# Decimal_Display_Electronic_Scheme_2021-1.net
KiCad netlist of a schematic drawn in Altium Designer
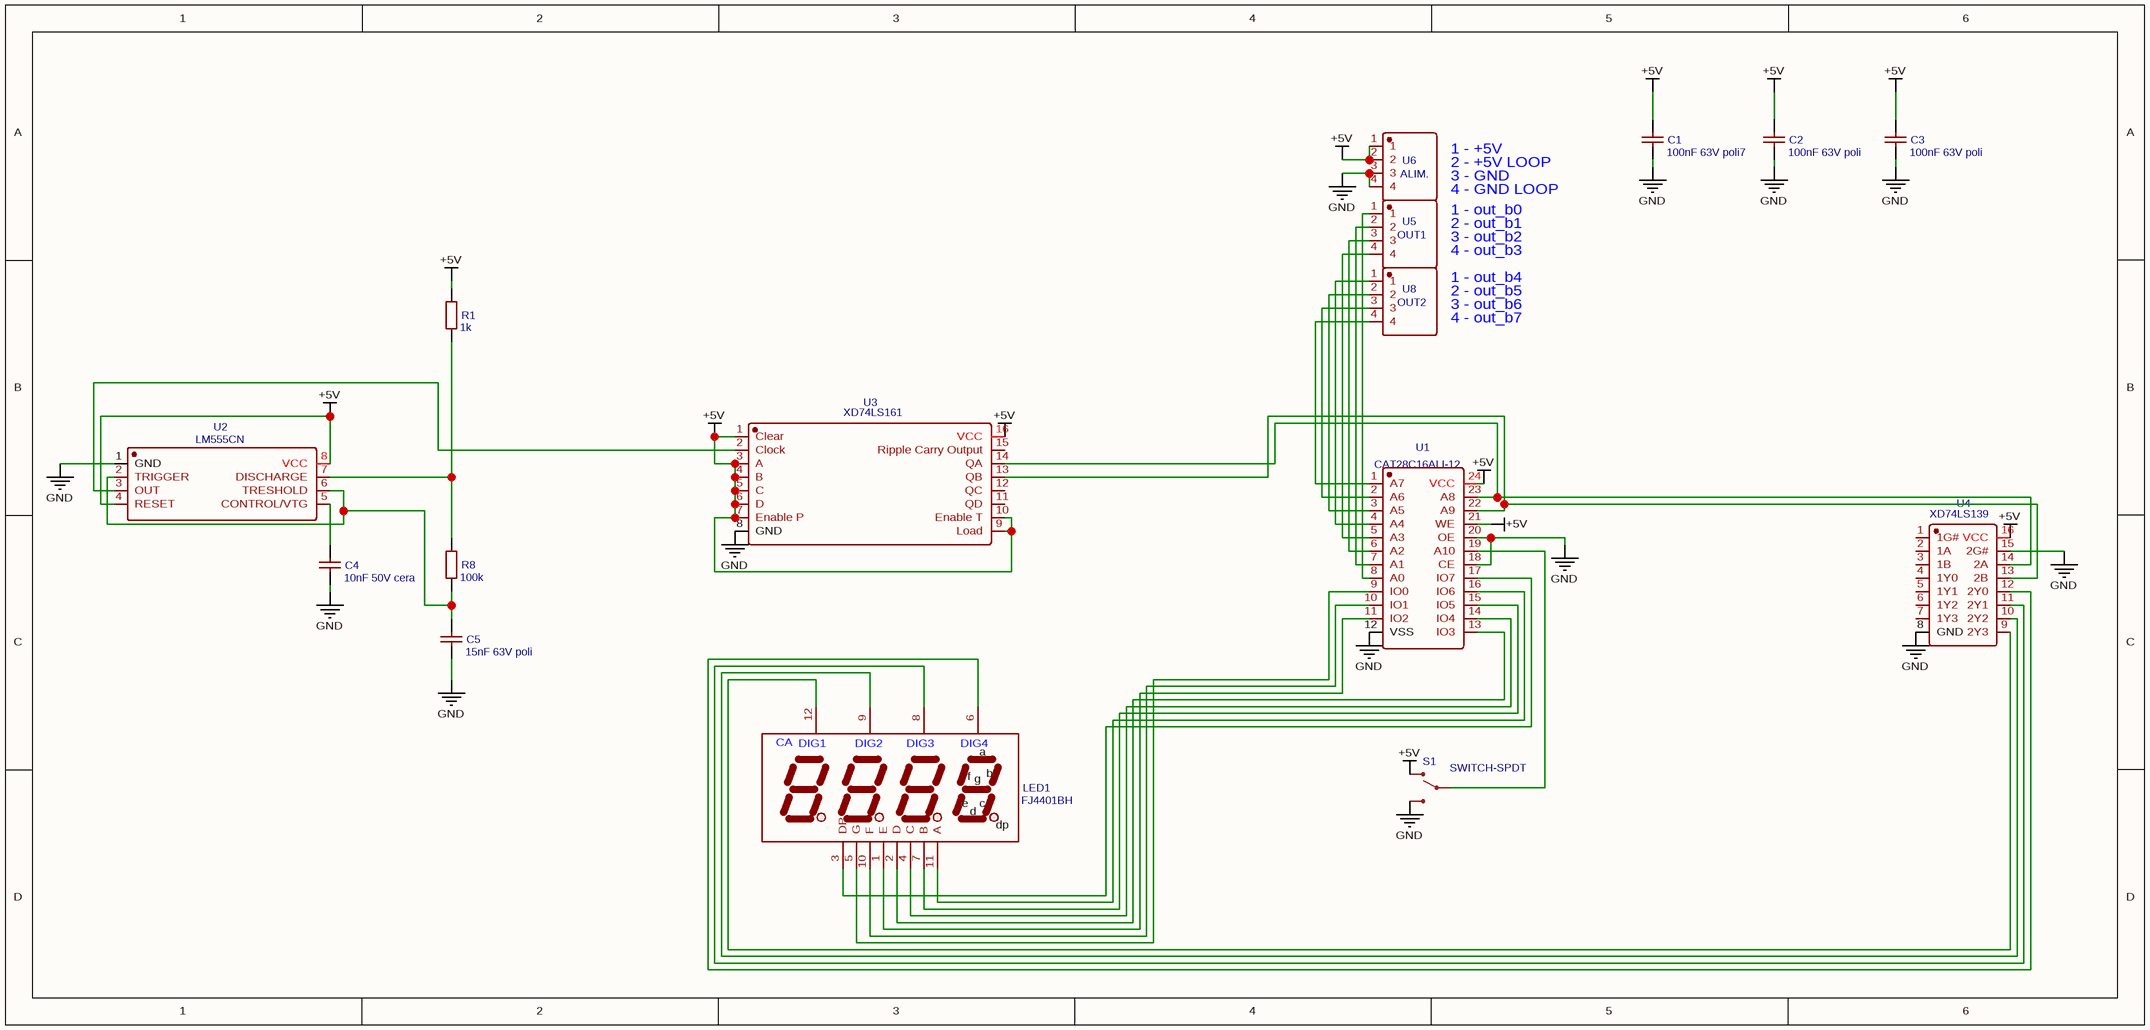
[diagram p0: Decimal Display Electronic Scheme_2021-10-08.schdoc]

(export (version "E")
  (design (tool "Eeschema 10.0.6"))
  (components
    (comp (ref "C1")
      (value "100nF 63V poli7")
      (fields
        (field (name "BOM_SUPPLIER PART") "C444741")
        (field (name "BOM_MANUFACTURER PART") "SR305C105KAR")
        (field (name "CONTRIBUTOR") "LCSC")
      )
      (libsource (lib "altium-import") (part "root_3_100nF 63V poli7_"))
    )
    (comp (ref "C2")
      (value "100nF 63V poli")
      (fields
        (field (name "BOM_SUPPLIER PART") "C444741")
        (field (name "BOM_MANUFACTURER PART") "SR305C105KAR")
        (field (name "CONTRIBUTOR") "LCSC")
      )
      (libsource (lib "altium-import") (part "root_3_100nF 63V poli_"))
    )
    (comp (ref "C3")
      (value "100nF 63V poli")
      (fields
        (field (name "BOM_SUPPLIER PART") "C444741")
        (field (name "BOM_MANUFACTURER PART") "SR305C105KAR")
        (field (name "CONTRIBUTOR") "LCSC")
      )
      (libsource (lib "altium-import") (part "root_3_100nF 63V poli_"))
    )
    (comp (ref "C4")
      (value "10nF 50V cera")
      (fields
        (field (name "BOM_SUPPLIER PART") "C444741")
        (field (name "BOM_MANUFACTURER PART") "SR305C105KAR")
        (field (name "CONTRIBUTOR") "LCSC")
      )
      (libsource (lib "altium-import") (part "root_3_10nF 50V cera_"))
    )
    (comp (ref "C5")
      (value "15nF 63V poli")
      (fields
        (field (name "BOM_SUPPLIER PART") "C444741")
        (field (name "BOM_MANUFACTURER PART") "SR305C105KAR")
        (field (name "CONTRIBUTOR") "LCSC")
      )
      (libsource (lib "altium-import") (part "root_3_15nF 63V poli_"))
    )
    (comp (ref "LED1")
      (value "FJ4401BH")
      (fields (field (name "BOM_SUPPLIER PART") "C10712"))
      (libsource (lib "altium-import") (part "root_0_FJ4401BH_"))
    )
    (comp (ref "R1")
      (value "1k")
      (fields
        (field (name "BOM_MANUFACTURER PART") "CFR02SJ0823A10")
        (field (name "BOM_SUPPLIER PART") "C69876")
      )
      (libsource (lib "altium-import") (part "root_3_1k_"))
    )
    (comp (ref "R8")
      (value "100k")
      (fields
        (field (name "BOM_MANUFACTURER PART") "CFR02SJ0823A10")
        (field (name "BOM_SUPPLIER PART") "C69876")
      )
      (libsource (lib "altium-import") (part "root_3_100k_"))
    )
    (comp (ref "S1")
      (value "SWITCH-SPDT")
      (fields (field (name "CONTRIBUTOR") "SparkFun"))
      (libsource (lib "altium-import") (part "root_0_SWITCH-SPDT_"))
    )
    (comp (ref "U1")
      (value "CAT28C16ALI-12")
      (libsource (lib "altium-import") (part "root_0_CAT28C16ALI-12_"))
    )
    (comp (ref "U2")
      (value "LM555CN")
      (fields (field (name "BOM_SUPPLIER PART") "C110322"))
      (libsource (lib "altium-import") (part "root_0_LM555CN_"))
    )
    (comp (ref "U3")
      (value "XD74LS161")
      (fields (field (name "BOM_SUPPLIER PART") "C609766") (field (name "CONTRIBUTOR") "LCSC"))
      (libsource (lib "altium-import") (part "root_0_XD74LS161_"))
    )
    (comp (ref "U4")
      (value "XD74LS139")
      (fields (field (name "BOM_SUPPLIER PART") "C521175") (field (name "CONTRIBUTOR") "LCSC"))
      (libsource (lib "altium-import") (part "root_0_XD74LS139_"))
    )
    (comp (ref "U5")
      (value "OUT1")
      (fields
        (field (name "BOM_SUPPLIER PART") "C210162")
        (field (name "BOM_MANUFACTURER PART") "171825-4")
        (field (name "CONTRIBUTOR") "LCSC")
      )
      (libsource (lib "altium-import") (part "root_0_OUT1_"))
    )
    (comp (ref "U6")
      (value "ALIM.")
      (fields
        (field (name "BOM_SUPPLIER PART") "C210162")
        (field (name "BOM_MANUFACTURER PART") "171825-4")
        (field (name "CONTRIBUTOR") "LCSC")
      )
      (libsource (lib "altium-import") (part "root_0_ALIM._"))
    )
    (comp (ref "U8")
      (value "OUT2")
      (fields
        (field (name "BOM_SUPPLIER PART") "C210162")
        (field (name "BOM_MANUFACTURER PART") "171825-4")
        (field (name "CONTRIBUTOR") "LCSC")
      )
      (libsource (lib "altium-import") (part "root_0_OUT2_"))
    )
  )
  (nets
    (net (code "1") (name "+5V") (class "Default")
      (node (ref "C1") (pin "1") (pinfunction "1_1") (pintype "passive"))
      (node (ref "C2") (pin "1") (pinfunction "1_1") (pintype "passive"))
      (node (ref "C3") (pin "1") (pinfunction "1_1") (pintype "passive"))
      (node (ref "R1") (pin "1") (pinfunction "1_1") (pintype "passive"))
      (node (ref "S1") (pin "1") (pinfunction "O_1") (pintype "passive"))
      (node (ref "U1") (pin "21") (pinfunction "WE_21") (pintype "passive"))
      (node (ref "U1") (pin "24") (pinfunction "VCC_24") (pintype "passive"))
      (node (ref "U2") (pin "4") (pinfunction "RESET_4") (pintype "passive"))
      (node (ref "U2") (pin "8") (pinfunction "VCC_8") (pintype "passive"))
      (node (ref "U3") (pin "1") (pinfunction "Clear_1") (pintype "passive"))
      (node (ref "U3") (pin "10") (pinfunction "Enable_T_10") (pintype "passive"))
      (node (ref "U3") (pin "16") (pinfunction "VCC_16") (pintype "passive"))
      (node (ref "U3") (pin "3") (pinfunction "A_3") (pintype "passive"))
      (node (ref "U3") (pin "4") (pinfunction "B_4") (pintype "passive"))
      (node (ref "U3") (pin "5") (pinfunction "C_5") (pintype "passive"))
      (node (ref "U3") (pin "6") (pinfunction "D_6") (pintype "passive"))
      (node (ref "U3") (pin "7") (pinfunction "Enable_P_7") (pintype "passive"))
      (node (ref "U3") (pin "9") (pinfunction "Load_9") (pintype "passive"))
      (node (ref "U4") (pin "16") (pinfunction "VCC_16") (pintype "passive"))
      (node (ref "U6") (pin "1") (pinfunction "1_1") (pintype "passive"))
      (node (ref "U6") (pin "2") (pinfunction "2_2") (pintype "passive"))
    )
    (net (code "2") (name "GND") (class "Default")
      (node (ref "C1") (pin "2") (pinfunction "2_2") (pintype "passive"))
      (node (ref "C2") (pin "2") (pinfunction "2_2") (pintype "passive"))
      (node (ref "C3") (pin "2") (pinfunction "2_2") (pintype "passive"))
      (node (ref "C4") (pin "2") (pinfunction "2_2") (pintype "passive"))
      (node (ref "C5") (pin "2") (pinfunction "2_2") (pintype "passive"))
      (node (ref "S1") (pin "3") (pinfunction "S_3") (pintype "passive"))
      (node (ref "U1") (pin "12") (pinfunction "VSS_12") (pintype "passive"))
      (node (ref "U1") (pin "18") (pinfunction "CE_18") (pintype "passive"))
      (node (ref "U1") (pin "20") (pinfunction "OE_20") (pintype "passive"))
      (node (ref "U2") (pin "1") (pinfunction "GND_1") (pintype "passive"))
      (node (ref "U3") (pin "8") (pinfunction "GND_8") (pintype "passive"))
      (node (ref "U4") (pin "15") (pinfunction "2G#_15") (pintype "passive"))
      (node (ref "U4") (pin "8") (pinfunction "GND_8") (pintype "passive"))
      (node (ref "U6") (pin "3") (pinfunction "3_3") (pintype "passive"))
      (node (ref "U6") (pin "4") (pinfunction "4_4") (pintype "passive"))
    )
    (net (code "3") (name "Net-(LED1-A)") (class "Default")
      (node (ref "LED1") (pin "11") (pinfunction "A_11") (pintype "passive"))
      (node (ref "U1") (pin "16") (pinfunction "IO6_16") (pintype "passive"))
    )
    (net (code "4") (name "Net-(LED1-B)") (class "Default")
      (node (ref "LED1") (pin "7") (pinfunction "B_7") (pintype "passive"))
      (node (ref "U1") (pin "15") (pinfunction "IO5_15") (pintype "passive"))
    )
    (net (code "5") (name "Net-(LED1-C)") (class "Default")
      (node (ref "LED1") (pin "4") (pinfunction "C_4") (pintype "passive"))
      (node (ref "U1") (pin "14") (pinfunction "IO4_14") (pintype "passive"))
    )
    (net (code "6") (name "Net-(LED1-D)") (class "Default")
      (node (ref "LED1") (pin "2") (pinfunction "D_2") (pintype "passive"))
      (node (ref "U1") (pin "13") (pinfunction "IO3_13") (pintype "passive"))
    )
    (net (code "7") (name "Net-(LED1-DIG1)") (class "Default")
      (node (ref "LED1") (pin "12") (pinfunction "DIG1_12") (pintype "passive"))
      (node (ref "U4") (pin "9") (pinfunction "2Y3_9") (pintype "passive"))
    )
    (net (code "8") (name "Net-(LED1-DIG2)") (class "Default")
      (node (ref "LED1") (pin "9") (pinfunction "DIG2_9") (pintype "passive"))
      (node (ref "U4") (pin "10") (pinfunction "2Y2_10") (pintype "passive"))
    )
    (net (code "9") (name "Net-(LED1-DIG3)") (class "Default")
      (node (ref "LED1") (pin "8") (pinfunction "DIG3_8") (pintype "passive"))
      (node (ref "U4") (pin "11") (pinfunction "2Y1_11") (pintype "passive"))
    )
    (net (code "10") (name "Net-(LED1-DIG4)") (class "Default")
      (node (ref "LED1") (pin "6") (pinfunction "DIG4_6") (pintype "passive"))
      (node (ref "U4") (pin "12") (pinfunction "2Y0_12") (pintype "passive"))
    )
    (net (code "11") (name "Net-(LED1-DP)") (class "Default")
      (node (ref "LED1") (pin "3") (pinfunction "DP_3") (pintype "passive"))
      (node (ref "U1") (pin "17") (pinfunction "IO7_17") (pintype "passive"))
    )
    (net (code "12") (name "Net-(LED1-E)") (class "Default")
      (node (ref "LED1") (pin "1") (pinfunction "E_1") (pintype "passive"))
      (node (ref "U1") (pin "11") (pinfunction "IO2_11") (pintype "passive"))
    )
    (net (code "13") (name "Net-(LED1-F)") (class "Default")
      (node (ref "LED1") (pin "10") (pinfunction "F_10") (pintype "passive"))
      (node (ref "U1") (pin "10") (pinfunction "IO1_10") (pintype "passive"))
    )
    (net (code "14") (name "Net-(LED1-G)") (class "Default")
      (node (ref "LED1") (pin "5") (pinfunction "G_5") (pintype "passive"))
      (node (ref "U1") (pin "9") (pinfunction "IO0_9") (pintype "passive"))
    )
    (net (code "15") (name "Net-(S1-P)") (class "Default")
      (node (ref "S1") (pin "2") (pinfunction "P_2") (pintype "passive"))
      (node (ref "U1") (pin "19") (pinfunction "A10_19") (pintype "passive"))
    )
    (net (code "16") (name "Net-(U1-A0)") (class "Default")
      (node (ref "U1") (pin "8") (pinfunction "A0_8") (pintype "passive"))
      (node (ref "U5") (pin "1") (pinfunction "1_1") (pintype "passive"))
    )
    (net (code "17") (name "Net-(U1-A1)") (class "Default")
      (node (ref "U1") (pin "7") (pinfunction "A1_7") (pintype "passive"))
      (node (ref "U5") (pin "2") (pinfunction "2_2") (pintype "passive"))
    )
    (net (code "18") (name "Net-(U1-A2)") (class "Default")
      (node (ref "U1") (pin "6") (pinfunction "A2_6") (pintype "passive"))
      (node (ref "U5") (pin "3") (pinfunction "3_3") (pintype "passive"))
    )
    (net (code "19") (name "Net-(U1-A3)") (class "Default")
      (node (ref "U1") (pin "5") (pinfunction "A3_5") (pintype "passive"))
      (node (ref "U5") (pin "4") (pinfunction "4_4") (pintype "passive"))
    )
    (net (code "20") (name "Net-(U1-A4)") (class "Default")
      (node (ref "U1") (pin "4") (pinfunction "A4_4") (pintype "passive"))
      (node (ref "U8") (pin "1") (pinfunction "1_1") (pintype "passive"))
    )
    (net (code "21") (name "Net-(U1-A5)") (class "Default")
      (node (ref "U1") (pin "3") (pinfunction "A5_3") (pintype "passive"))
      (node (ref "U8") (pin "2") (pinfunction "2_2") (pintype "passive"))
    )
    (net (code "22") (name "Net-(U1-A6)") (class "Default")
      (node (ref "U1") (pin "2") (pinfunction "A6_2") (pintype "passive"))
      (node (ref "U8") (pin "3") (pinfunction "3_3") (pintype "passive"))
    )
    (net (code "23") (name "Net-(U1-A7)") (class "Default")
      (node (ref "U1") (pin "1") (pinfunction "A7_1") (pintype "passive"))
      (node (ref "U8") (pin "4") (pinfunction "4_4") (pintype "passive"))
    )
    (net (code "24") (name "Net-(U1-A8)") (class "Default")
      (node (ref "U1") (pin "23") (pinfunction "A8_23") (pintype "passive"))
      (node (ref "U3") (pin "14") (pinfunction "QA_14") (pintype "passive"))
      (node (ref "U4") (pin "14") (pinfunction "2A_14") (pintype "passive"))
    )
    (net (code "25") (name "Net-(U1-A9)") (class "Default")
      (node (ref "U1") (pin "22") (pinfunction "A9_22") (pintype "passive"))
      (node (ref "U3") (pin "13") (pinfunction "QB_13") (pintype "passive"))
      (node (ref "U4") (pin "13") (pinfunction "2B_13") (pintype "passive"))
    )
    (net (code "26") (name "Net-(U2-CONTROL{slash}VTG)") (class "Default")
      (node (ref "C4") (pin "1") (pinfunction "1_1") (pintype "passive"))
      (node (ref "U2") (pin "5") (pinfunction "CONTROL/VTG_5") (pintype "passive"))
    )
    (net (code "27") (name "Net-(U2-DISCHARGE)") (class "Default")
      (node (ref "R1") (pin "2") (pinfunction "2_2") (pintype "passive"))
      (node (ref "R8") (pin "1") (pinfunction "1_1") (pintype "passive"))
      (node (ref "U2") (pin "7") (pinfunction "DISCHARGE_7") (pintype "passive"))
    )
    (net (code "28") (name "Net-(U2-OUT)") (class "Default")
      (node (ref "U2") (pin "3") (pinfunction "OUT_3") (pintype "passive"))
      (node (ref "U3") (pin "2") (pinfunction "Clock_2") (pintype "passive"))
    )
    (net (code "29") (name "Net-(U2-TRESHOLD)") (class "Default")
      (node (ref "C5") (pin "1") (pinfunction "1_1") (pintype "passive"))
      (node (ref "R8") (pin "2") (pinfunction "2_2") (pintype "passive"))
      (node (ref "U2") (pin "2") (pinfunction "TRIGGER_2") (pintype "passive"))
      (node (ref "U2") (pin "6") (pinfunction "TRESHOLD_6") (pintype "passive"))
    )
    (net (code "30") (name "unconnected-(U3-QC-Pad12)") (class "Default")
      (node (ref "U3") (pin "12") (pinfunction "QC_12") (pintype "passive"))
    )
    (net (code "31") (name "unconnected-(U3-QD-Pad11)") (class "Default")
      (node (ref "U3") (pin "11") (pinfunction "QD_11") (pintype "passive"))
    )
    (net (code "32") (name "unconnected-(U3-Ripple_Carry_Output-Pad15)") (class "Default")
      (node (ref "U3") (pin "15") (pinfunction "Ripple_Carry_Output_15") (pintype "passive"))
    )
    (net (code "33") (name "unconnected-(U4-1A-Pad2)") (class "Default")
      (node (ref "U4") (pin "2") (pinfunction "1A_2") (pintype "passive"))
    )
    (net (code "34") (name "unconnected-(U4-1B-Pad3)") (class "Default")
      (node (ref "U4") (pin "3") (pinfunction "1B_3") (pintype "passive"))
    )
    (net (code "35") (name "unconnected-(U4-1G#-Pad1)") (class "Default")
      (node (ref "U4") (pin "1") (pinfunction "1G#_1") (pintype "passive"))
    )
    (net (code "36") (name "unconnected-(U4-1Y0-Pad4)") (class "Default")
      (node (ref "U4") (pin "4") (pinfunction "1Y0_4") (pintype "passive"))
    )
    (net (code "37") (name "unconnected-(U4-1Y1-Pad5)") (class "Default")
      (node (ref "U4") (pin "5") (pinfunction "1Y1_5") (pintype "passive"))
    )
    (net (code "38") (name "unconnected-(U4-1Y2-Pad6)") (class "Default")
      (node (ref "U4") (pin "6") (pinfunction "1Y2_6") (pintype "passive"))
    )
    (net (code "39") (name "unconnected-(U4-1Y3-Pad7)") (class "Default")
      (node (ref "U4") (pin "7") (pinfunction "1Y3_7") (pintype "passive"))
    )
  )
)
